# Microcontroller.net
KiCad netlist of a schematic drawn in Altium Designer
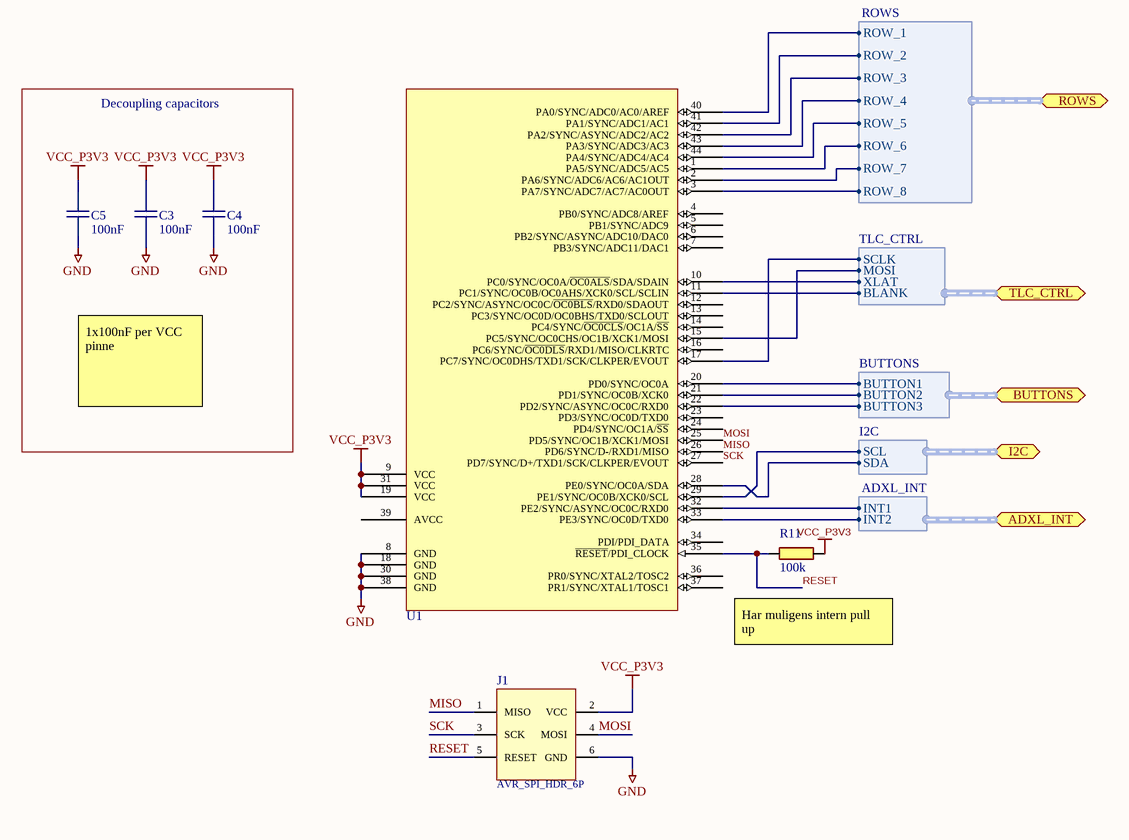
[diagram p0: Microcontroller.SchDoc]

(export (version "E")
  (design (tool "Eeschema 10.0.6"))
  (components
    (comp (ref "C3")
      (value "100nF")
      (footprint "CAPC0805(2012)100_N")
      (description "X7R 50V")
      (libsource (lib "OVLib") (part "CAP"))
    )
    (comp (ref "C4")
      (value "100nF")
      (footprint "CAPC0805(2012)100_N")
      (description "X7R 50V")
      (libsource (lib "OVLib") (part "CAP"))
    )
    (comp (ref "C5")
      (value "100nF")
      (footprint "CAPC0805(2012)100_N")
      (description "X7R 50V")
      (libsource (lib "OVLib") (part "CAP"))
    )
    (comp (ref "J1")
      (value "AVR_SPI_HDR_6P")
      (footprint "HEADER_3x2")
      (description "6-pins ISP header for AVR")
      (libsource (lib "OVLib") (part "AVR_SPI_HDR_6P"))
    )
    (comp (ref "R11")
      (value "100k")
      (footprint "RESC0603(1608)_N")
      (description "0.1W 1% Thick film resistor")
      (libsource (lib "OVLib") (part "Resistor2"))
    )
    (comp (ref "U1")
      (value "ATXMEGA-A4U")
      (footprint "TQFP80P1200X1200X120-44N")
      (libsource (lib "OVLib") (part "ATXMEGA-A4U"))
    )
  )
  (nets
    (net (code "6") (name "/BLANK") (class "Default")
      (node (ref "U1") (pin "11") (pinfunction "PC1/SYNC/OC0B/OC0AHS/XCK0/SCL/SCLIN_11") (pintype "bidirectional"))
    )
    (net (code "7") (name "/BUTTON1") (class "Default")
      (node (ref "U1") (pin "20") (pinfunction "PD0/SYNC/OC0A_20") (pintype "bidirectional"))
    )
    (net (code "8") (name "/BUTTON2") (class "Default")
      (node (ref "U1") (pin "21") (pinfunction "PD1/SYNC/OC0B/XCK0_21") (pintype "bidirectional"))
    )
    (net (code "9") (name "/BUTTON3") (class "Default")
      (node (ref "U1") (pin "22") (pinfunction "PD2/SYNC/ASYNC/OC0C/RXD0_22") (pintype "bidirectional"))
    )
    (net (code "10") (name "/INT1") (class "Default")
      (node (ref "U1") (pin "32") (pinfunction "PE2/SYNC/ASYNC/OC0C/RXD0_32") (pintype "bidirectional"))
    )
    (net (code "11") (name "/INT2") (class "Default")
      (node (ref "U1") (pin "33") (pinfunction "PE3/SYNC/OC0D/TXD0_33") (pintype "bidirectional"))
    )
    (net (code "12") (name "/MISO") (class "Default")
      (node (ref "J1") (pin "1") (pinfunction "MISO_1") (pintype "passive"))
      (node (ref "U1") (pin "26") (pinfunction "PD6/SYNC/D-/RXD1/MISO_26") (pintype "bidirectional"))
    )
    (net (code "13") (name "/MOSI") (class "Default")
      (node (ref "J1") (pin "4") (pinfunction "MOSI_4") (pintype "passive"))
      (node (ref "U1") (pin "25") (pinfunction "PD5/SYNC/OC1B/XCK1/MOSI_25") (pintype "bidirectional"))
    )
    (net (code "14") (name "/RESET") (class "Default")
      (node (ref "J1") (pin "5") (pinfunction "RESET_5") (pintype "passive"))
      (node (ref "R11") (pin "2") (pinfunction "2_2") (pintype "passive"))
      (node (ref "U1") (pin "35") (pinfunction "~{RESET}/PDI_CLOCK_35") (pintype "input"))
    )
    (net (code "15") (name "/ROW_1") (class "Default")
      (node (ref "U1") (pin "40") (pinfunction "PA0/SYNC/ADC0/AC0/AREF_40") (pintype "bidirectional"))
    )
    (net (code "16") (name "/ROW_2") (class "Default")
      (node (ref "U1") (pin "41") (pinfunction "PA1/SYNC/ADC1/AC1_41") (pintype "bidirectional"))
    )
    (net (code "17") (name "/ROW_3") (class "Default")
      (node (ref "U1") (pin "42") (pinfunction "PA2/SYNC/ASYNC/ADC2/AC2_42") (pintype "bidirectional"))
    )
    (net (code "18") (name "/ROW_4") (class "Default")
      (node (ref "U1") (pin "43") (pinfunction "PA3/SYNC/ADC3/AC3_43") (pintype "bidirectional"))
    )
    (net (code "19") (name "/ROW_5") (class "Default")
      (node (ref "U1") (pin "44") (pinfunction "PA4/SYNC/ADC4/AC4_44") (pintype "bidirectional"))
    )
    (net (code "20") (name "/ROW_6") (class "Default")
      (node (ref "U1") (pin "1") (pinfunction "PA5/SYNC/ADC5/AC5_1") (pintype "bidirectional"))
    )
    (net (code "21") (name "/ROW_7") (class "Default")
      (node (ref "U1") (pin "2") (pinfunction "PA6/SYNC/ADC6/AC6/AC1OUT_2") (pintype "bidirectional"))
    )
    (net (code "22") (name "/ROW_8") (class "Default")
      (node (ref "U1") (pin "3") (pinfunction "PA7/SYNC/ADC7/AC7/AC0OUT_3") (pintype "bidirectional"))
    )
    (net (code "23") (name "/SCK") (class "Default")
      (node (ref "J1") (pin "3") (pinfunction "SCK_3") (pintype "passive"))
      (node (ref "U1") (pin "27") (pinfunction "PD7/SYNC/D+/TXD1/SCK/CLKPER/EVOUT_27") (pintype "bidirectional"))
    )
    (net (code "24") (name "/SCL") (class "Default")
      (node (ref "U1") (pin "29") (pinfunction "PE1/SYNC/OC0B/XCK0/SCL_29") (pintype "bidirectional"))
    )
    (net (code "25") (name "/SCLK") (class "Default")
      (node (ref "U1") (pin "17") (pinfunction "PC7/SYNC/OC0DHS/TXD1/SCK/CLKPER/EVOUT_17") (pintype "bidirectional"))
    )
    (net (code "26") (name "/SDA") (class "Default")
      (node (ref "U1") (pin "28") (pinfunction "PE0/SYNC/OC0A/SDA_28") (pintype "bidirectional"))
    )
    (net (code "27") (name "/XLAT") (class "Default")
      (node (ref "U1") (pin "10") (pinfunction "PC0/SYNC/OC0A/~{OC0ALS}/SDA/SDAIN_10") (pintype "bidirectional"))
    )
    (net (code "33") (name "GND") (class "Default")
      (node (ref "C3") (pin "1") (pinfunction "1_1") (pintype "passive"))
      (node (ref "C4") (pin "1") (pinfunction "1_1") (pintype "passive"))
      (node (ref "C5") (pin "1") (pinfunction "1_1") (pintype "passive"))
      (node (ref "J1") (pin "6") (pinfunction "GND_6") (pintype "passive"))
      (node (ref "U1") (pin "18") (pinfunction "GND_18") (pintype "power_in"))
      (node (ref "U1") (pin "30") (pinfunction "GND_30") (pintype "power_in"))
      (node (ref "U1") (pin "38") (pinfunction "GND_38") (pintype "power_in"))
      (node (ref "U1") (pin "8") (pinfunction "GND_8") (pintype "power_in"))
    )
    (net (code "34") (name "VCC_P3V3") (class "Default")
      (node (ref "C3") (pin "2") (pinfunction "2_2") (pintype "passive"))
      (node (ref "C4") (pin "2") (pinfunction "2_2") (pintype "passive"))
      (node (ref "C5") (pin "2") (pinfunction "2_2") (pintype "passive"))
      (node (ref "J1") (pin "2") (pinfunction "VCC_2") (pintype "passive"))
      (node (ref "R11") (pin "1") (pinfunction "1_1") (pintype "passive"))
      (node (ref "U1") (pin "19") (pinfunction "VCC_19") (pintype "power_in"))
      (node (ref "U1") (pin "31") (pinfunction "VCC_31") (pintype "power_in"))
      (node (ref "U1") (pin "9") (pinfunction "VCC_9") (pintype "power_in"))
    )
    (net (code "35") (name "unconnected-(U1-AVCC-Pad39)") (class "Default")
      (node (ref "U1") (pin "39") (pinfunction "AVCC_39") (pintype "power_in"))
    )
    (net (code "36") (name "unconnected-(U1-PB0{slash}SYNC{slash}ADC8{slash}AREF-Pad4)") (class "Default")
      (node (ref "U1") (pin "4") (pinfunction "PB0/SYNC/ADC8/AREF_4") (pintype "bidirectional"))
    )
    (net (code "37") (name "unconnected-(U1-PB1{slash}SYNC{slash}ADC9-Pad5)") (class "Default")
      (node (ref "U1") (pin "5") (pinfunction "PB1/SYNC/ADC9_5") (pintype "bidirectional"))
    )
    (net (code "38") (name "unconnected-(U1-PB2{slash}SYNC{slash}ASYNC{slash}ADC10{slash}DAC0-Pad6)") (class "Default")
      (node (ref "U1") (pin "6") (pinfunction "PB2/SYNC/ASYNC/ADC10/DAC0_6") (pintype "bidirectional"))
    )
    (net (code "39") (name "unconnected-(U1-PB3{slash}SYNC{slash}ADC11{slash}DAC1-Pad7)") (class "Default")
      (node (ref "U1") (pin "7") (pinfunction "PB3/SYNC/ADC11/DAC1_7") (pintype "bidirectional"))
    )
    (net (code "40") (name "unconnected-(U1-PC2{slash}SYNC{slash}ASYNC{slash}OC0C{slash}~{OC0BLS}{slash}RXD0{slash}SDAOUT-Pad12)") (class "Default")
      (node (ref "U1") (pin "12") (pinfunction "PC2/SYNC/ASYNC/OC0C/~{OC0BLS}/RXD0/SDAOUT_12") (pintype "bidirectional"))
    )
    (net (code "41") (name "unconnected-(U1-PC3{slash}SYNC{slash}OC0D{slash}OC0BHS{slash}TXD0{slash}SCLOUT-Pad13)") (class "Default")
      (node (ref "U1") (pin "13") (pinfunction "PC3/SYNC/OC0D/OC0BHS/TXD0/SCLOUT_13") (pintype "bidirectional"))
    )
    (net (code "42") (name "unconnected-(U1-PC4{slash}SYNC{slash}~{OC0CLS}{slash}OC1A{slash}~{SS}-Pad14)") (class "Default")
      (node (ref "U1") (pin "14") (pinfunction "PC4/SYNC/~{OC0CLS}/OC1A/~{SS}_14") (pintype "bidirectional"))
    )
    (net (code "43") (name "unconnected-(U1-PC5{slash}SYNC{slash}OC0CHS{slash}OC1B{slash}XCK1{slash}MOSI-Pad15)") (class "Default")
      (node (ref "U1") (pin "15") (pinfunction "PC5/SYNC/OC0CHS/OC1B/XCK1/MOSI_15") (pintype "bidirectional"))
    )
    (net (code "44") (name "unconnected-(U1-PC6{slash}SYNC{slash}~{OC0DLS}{slash}RXD1{slash}MISO{slash}CLKRTC-Pad16)") (class "Default")
      (node (ref "U1") (pin "16") (pinfunction "PC6/SYNC/~{OC0DLS}/RXD1/MISO/CLKRTC_16") (pintype "bidirectional"))
    )
    (net (code "45") (name "unconnected-(U1-PD3{slash}SYNC{slash}OC0D{slash}TXD0-Pad23)") (class "Default")
      (node (ref "U1") (pin "23") (pinfunction "PD3/SYNC/OC0D/TXD0_23") (pintype "bidirectional"))
    )
    (net (code "46") (name "unconnected-(U1-PD4{slash}SYNC{slash}OC1A{slash}~{SS}-Pad24)") (class "Default")
      (node (ref "U1") (pin "24") (pinfunction "PD4/SYNC/OC1A/~{SS}_24") (pintype "bidirectional"))
    )
    (net (code "47") (name "unconnected-(U1-PDI{slash}PDI_DATA-Pad34)") (class "Default")
      (node (ref "U1") (pin "34") (pinfunction "PDI/PDI_DATA_34") (pintype "bidirectional"))
    )
    (net (code "48") (name "unconnected-(U1-PR0{slash}SYNC{slash}XTAL2{slash}TOSC2-Pad36)") (class "Default")
      (node (ref "U1") (pin "36") (pinfunction "PR0/SYNC/XTAL2/TOSC2_36") (pintype "bidirectional"))
    )
    (net (code "49") (name "unconnected-(U1-PR1{slash}SYNC{slash}XTAL1{slash}TOSC1-Pad37)") (class "Default")
      (node (ref "U1") (pin "37") (pinfunction "PR1/SYNC/XTAL1/TOSC1_37") (pintype "bidirectional"))
    )
  )
)
